# intex_spa_V4.net
KiCad netlist of a schematic drawn in EAGLE
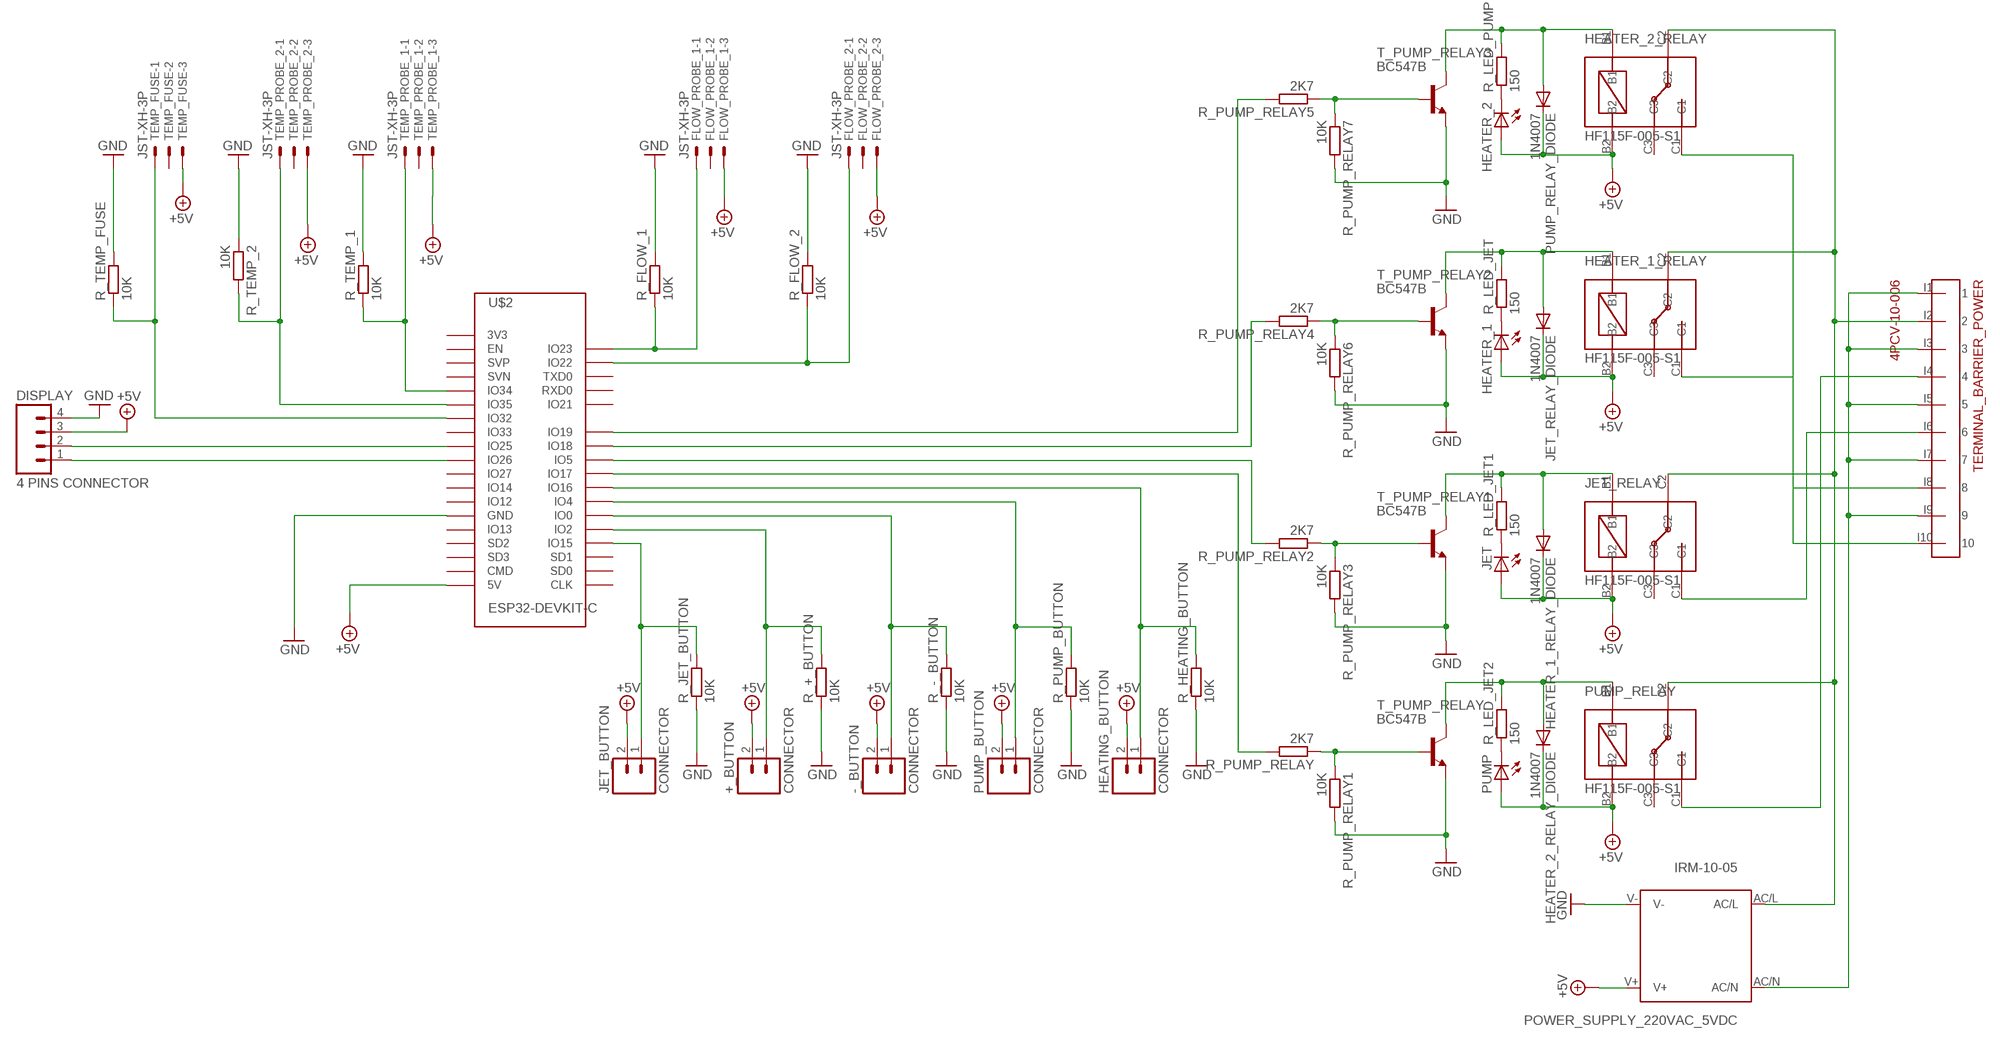
[diagram p0: schematic, sheet 1]

(export (version "E")
  (design (tool "Eeschema 10.0.6"))
  (components
    (comp (ref "+_BUTTON")
      (value "CONNECTOR")
      (footprint "eagle-import:JST-2-PTH-VERT")
      (libsource (lib "eagle-import") (part "M02JST-PTH-VERT"))
    )
    (comp (ref "-_BUTTON")
      (value "CONNECTOR")
      (footprint "eagle-import:JST-2-PTH-VERT")
      (libsource (lib "eagle-import") (part "M02JST-PTH-VERT"))
    )
    (comp (ref "DISPLAY")
      (value "4 PINS CONNECTOR")
      (footprint "eagle-import:1X04")
      (libsource (lib "eagle-import") (part "M04PTH"))
    )
    (comp (ref "FLOW_PROBE_1")
      (value "JST-XH-3P")
      (footprint "eagle-import:JST-XH-03-PACKAGE-LONG-PAD")
      (libsource (lib "eagle-import") (part "JST-XH-03-PIN-LONG-PAD"))
    )
    (comp (ref "FLOW_PROBE_2")
      (value "JST-XH-3P")
      (footprint "eagle-import:JST-XH-03-PACKAGE-LONG-PAD")
      (libsource (lib "eagle-import") (part "JST-XH-03-PIN-LONG-PAD"))
    )
    (comp (ref "HEATER_1")
      (value "LED3MM")
      (footprint "eagle-import:LED3MM")
      (libsource (lib "eagle-import") (part "LED3MM"))
    )
    (comp (ref "HEATER_1_RELAY")
      (value "HF115F-005-S1")
      (footprint "eagle-import:HF115F-005-S1")
      (libsource (lib "eagle-import") (part "HF115F-005-S1"))
    )
    (comp (ref "HEATER_1_RELAY_DIODE")
      (value "1N4007")
      (footprint "eagle-import:DO41-10")
      (libsource (lib "eagle-import") (part "1N4004"))
    )
    (comp (ref "HEATER_2")
      (value "LED3MM")
      (footprint "eagle-import:LED3MM")
      (libsource (lib "eagle-import") (part "LED3MM"))
    )
    (comp (ref "HEATER_2_RELAY")
      (value "HF115F-005-S1")
      (footprint "eagle-import:HF115F-005-S1")
      (libsource (lib "eagle-import") (part "HF115F-005-S1"))
    )
    (comp (ref "HEATER_2_RELAY_DIODE")
      (value "1N4007")
      (footprint "eagle-import:DO41-10")
      (libsource (lib "eagle-import") (part "1N4004"))
    )
    (comp (ref "HEATING_BUTTON")
      (value "CONNECTOR")
      (footprint "eagle-import:JST-2-PTH-VERT")
      (libsource (lib "eagle-import") (part "M02JST-PTH-VERT"))
    )
    (comp (ref "JET")
      (value "LED3MM")
      (footprint "eagle-import:LED3MM")
      (libsource (lib "eagle-import") (part "LED3MM"))
    )
    (comp (ref "JET_BUTTON")
      (value "CONNECTOR")
      (footprint "eagle-import:JST-2-PTH-VERT")
      (libsource (lib "eagle-import") (part "M02JST-PTH-VERT"))
    )
    (comp (ref "JET_RELAY")
      (value "HF115F-005-S1")
      (footprint "eagle-import:HF115F-005-S1")
      (libsource (lib "eagle-import") (part "HF115F-005-S1"))
    )
    (comp (ref "JET_RELAY_DIODE")
      (value "1N4007")
      (footprint "eagle-import:DO41-10")
      (libsource (lib "eagle-import") (part "1N4004"))
    )
    (comp (ref "POWER_SUPPLY_220VAC_5VDC")
      (value "IRM-10-05")
      (footprint "eagle-import:IRM_05_10")
      (libsource (lib "eagle-import") (part "IRM_05/10IRM_05/10"))
    )
    (comp (ref "PUMP")
      (value "LED3MM")
      (footprint "eagle-import:LED3MM")
      (libsource (lib "eagle-import") (part "LED3MM"))
    )
    (comp (ref "PUMP_BUTTON")
      (value "CONNECTOR")
      (footprint "eagle-import:JST-2-PTH-VERT")
      (libsource (lib "eagle-import") (part "M02JST-PTH-VERT"))
    )
    (comp (ref "PUMP_RELAY")
      (value "HF115F-005-S1")
      (footprint "eagle-import:HF115F-005-S1")
      (libsource (lib "eagle-import") (part "HF115F-005-S1"))
    )
    (comp (ref "PUMP_RELAY_DIODE")
      (value "1N4007")
      (footprint "eagle-import:DO41-10")
      (libsource (lib "eagle-import") (part "1N4004"))
    )
    (comp (ref "R_+_BUTTON")
      (value "10K")
      (footprint "eagle-import:0204_5")
      (libsource (lib "eagle-import") (part "R-EU_0204/5"))
    )
    (comp (ref "R_-_BUTTON")
      (value "10K")
      (footprint "eagle-import:0204_5")
      (libsource (lib "eagle-import") (part "R-EU_0204/5"))
    )
    (comp (ref "R_FLOW_1")
      (value "10K")
      (footprint "eagle-import:0207_10")
      (libsource (lib "eagle-import") (part "R-EU_0207/10"))
    )
    (comp (ref "R_FLOW_2")
      (value "10K")
      (footprint "eagle-import:0207_10")
      (libsource (lib "eagle-import") (part "R-EU_0207/10"))
    )
    (comp (ref "R_HEATING_BUTTON")
      (value "10K")
      (footprint "eagle-import:0204_5")
      (libsource (lib "eagle-import") (part "R-EU_0204/5"))
    )
    (comp (ref "R_JET_BUTTON")
      (value "10K")
      (footprint "eagle-import:0204_5")
      (libsource (lib "eagle-import") (part "R-EU_0204/5"))
    )
    (comp (ref "R_LED_JET")
      (value "150")
      (footprint "eagle-import:0204_5")
      (libsource (lib "eagle-import") (part "resistor_R-EU_0204/5"))
    )
    (comp (ref "R_LED_JET1")
      (value "150")
      (footprint "eagle-import:0204_5")
      (libsource (lib "eagle-import") (part "resistor_R-EU_0204/5"))
    )
    (comp (ref "R_LED_JET2")
      (value "150")
      (footprint "eagle-import:0204_5")
      (libsource (lib "eagle-import") (part "resistor_R-EU_0204/5"))
    )
    (comp (ref "R_LED_PUMP")
      (value "150")
      (footprint "eagle-import:0204_5")
      (libsource (lib "eagle-import") (part "resistor_R-EU_0204/5"))
    )
    (comp (ref "R_PUMP_BUTTON")
      (value "10K")
      (footprint "eagle-import:0204_5")
      (libsource (lib "eagle-import") (part "R-EU_0204/5"))
    )
    (comp (ref "R_PUMP_RELAY")
      (value "2K7")
      (footprint "eagle-import:0204_5")
      (libsource (lib "eagle-import") (part "R-EU_0204/5"))
    )
    (comp (ref "R_PUMP_RELAY1")
      (value "10K")
      (footprint "eagle-import:0204_5")
      (libsource (lib "eagle-import") (part "R-EU_0204/5"))
    )
    (comp (ref "R_PUMP_RELAY2")
      (value "2K7")
      (footprint "eagle-import:0204_5")
      (libsource (lib "eagle-import") (part "R-EU_0204/5"))
    )
    (comp (ref "R_PUMP_RELAY3")
      (value "10K")
      (footprint "eagle-import:0204_5")
      (libsource (lib "eagle-import") (part "R-EU_0204/5"))
    )
    (comp (ref "R_PUMP_RELAY4")
      (value "2K7")
      (footprint "eagle-import:0204_5")
      (libsource (lib "eagle-import") (part "R-EU_0204/5"))
    )
    (comp (ref "R_PUMP_RELAY5")
      (value "2K7")
      (footprint "eagle-import:0204_5")
      (libsource (lib "eagle-import") (part "R-EU_0204/5"))
    )
    (comp (ref "R_PUMP_RELAY6")
      (value "10K")
      (footprint "eagle-import:0204_5")
      (libsource (lib "eagle-import") (part "R-EU_0204/5"))
    )
    (comp (ref "R_PUMP_RELAY7")
      (value "10K")
      (footprint "eagle-import:0204_5")
      (libsource (lib "eagle-import") (part "R-EU_0204/5"))
    )
    (comp (ref "R_TEMP_1")
      (value "10K")
      (footprint "eagle-import:0207_10")
      (libsource (lib "eagle-import") (part "R-EU_0207/10"))
    )
    (comp (ref "R_TEMP_2")
      (value "10K")
      (footprint "eagle-import:0207_10")
      (libsource (lib "eagle-import") (part "R-EU_0207/10"))
    )
    (comp (ref "R_TEMP_FUSE")
      (value "10K")
      (footprint "eagle-import:0207_10")
      (libsource (lib "eagle-import") (part "R-EU_0207/10"))
    )
    (comp (ref "TEMP_FUSE")
      (value "JST-XH-3P")
      (footprint "eagle-import:JST-XH-03-PACKAGE-LONG-PAD")
      (libsource (lib "eagle-import") (part "JST-XH-03-PIN-LONG-PAD"))
    )
    (comp (ref "TEMP_PROBE_1")
      (value "JST-XH-3P")
      (footprint "eagle-import:JST-XH-03-PACKAGE-LONG-PAD")
      (libsource (lib "eagle-import") (part "JST-XH-03-PIN-LONG-PAD"))
    )
    (comp (ref "TEMP_PROBE_2")
      (value "JST-XH-3P")
      (footprint "eagle-import:JST-XH-03-PACKAGE-LONG-PAD")
      (libsource (lib "eagle-import") (part "JST-XH-03-PIN-LONG-PAD"))
    )
    (comp (ref "TERMINAL_BARRIER_POWER")
      (value "4PCV-10-006")
      (footprint "eagle-import:4PCV-10-006")
      (libsource (lib "eagle-import") (part "4PCV-10-006"))
    )
    (comp (ref "T_PUMP_RELAY")
      (value "BC547B")
      (footprint "eagle-import:TO92")
      (libsource (lib "eagle-import") (part "BC547B"))
    )
    (comp (ref "T_PUMP_RELAY1")
      (value "BC547B")
      (footprint "eagle-import:TO92")
      (libsource (lib "eagle-import") (part "BC547B"))
    )
    (comp (ref "T_PUMP_RELAY2")
      (value "BC547B")
      (footprint "eagle-import:TO92")
      (libsource (lib "eagle-import") (part "BC547B"))
    )
    (comp (ref "T_PUMP_RELAY3")
      (value "BC547B")
      (footprint "eagle-import:TO92")
      (libsource (lib "eagle-import") (part "BC547B"))
    )
    (comp (ref "U$2")
      (value "ESP32-DEVKIT-C")
      (footprint "eagle-import:ESP32-DEVKIT-C")
      (libsource (lib "eagle-import") (part "ESP32-DEVKIT-C"))
    )
  )
  (nets
    (net (code "1") (name "+5V") (class "Default")
      (node (ref "+_BUTTON") (pin "2") (pinfunction "2_2") (pintype "passive"))
      (node (ref "-_BUTTON") (pin "2") (pinfunction "2_2") (pintype "passive"))
      (node (ref "DISPLAY") (pin "3") (pinfunction "3_3") (pintype "passive"))
      (node (ref "FLOW_PROBE_1") (pin "3") (pinfunction "S_3") (pintype "passive"))
      (node (ref "FLOW_PROBE_2") (pin "3") (pinfunction "S_3") (pintype "passive"))
      (node (ref "HEATER_1") (pin "A") (pinfunction "A_A") (pintype "passive"))
      (node (ref "HEATER_1_RELAY") (pin "B2") (pinfunction "B2_B2") (pintype "bidirectional"))
      (node (ref "HEATER_1_RELAY_DIODE") (pin "C") (pinfunction "C_C") (pintype "passive"))
      (node (ref "HEATER_2") (pin "A") (pinfunction "A_A") (pintype "passive"))
      (node (ref "HEATER_2_RELAY") (pin "B2") (pinfunction "B2_B2") (pintype "bidirectional"))
      (node (ref "HEATER_2_RELAY_DIODE") (pin "C") (pinfunction "C_C") (pintype "passive"))
      (node (ref "HEATING_BUTTON") (pin "2") (pinfunction "2_2") (pintype "passive"))
      (node (ref "JET") (pin "A") (pinfunction "A_A") (pintype "passive"))
      (node (ref "JET_BUTTON") (pin "2") (pinfunction "2_2") (pintype "passive"))
      (node (ref "JET_RELAY") (pin "B2") (pinfunction "B2_B2") (pintype "bidirectional"))
      (node (ref "JET_RELAY_DIODE") (pin "C") (pinfunction "C_C") (pintype "passive"))
      (node (ref "POWER_SUPPLY_220VAC_5VDC") (pin "V+") (pinfunction "V+_V+") (pintype "output"))
      (node (ref "PUMP") (pin "A") (pinfunction "A_A") (pintype "passive"))
      (node (ref "PUMP_BUTTON") (pin "2") (pinfunction "2_2") (pintype "passive"))
      (node (ref "PUMP_RELAY") (pin "B2") (pinfunction "B2_B2") (pintype "bidirectional"))
      (node (ref "PUMP_RELAY_DIODE") (pin "C") (pinfunction "C_C") (pintype "passive"))
      (node (ref "TEMP_FUSE") (pin "3") (pinfunction "S_3") (pintype "passive"))
      (node (ref "TEMP_PROBE_1") (pin "3") (pinfunction "S_3") (pintype "passive"))
      (node (ref "TEMP_PROBE_2") (pin "3") (pinfunction "S_3") (pintype "passive"))
      (node (ref "U$2") (pin "5V") (pinfunction "5V_5V") (pintype "bidirectional"))
    )
    (net (code "2") (name "GND") (class "Default")
      (node (ref "DISPLAY") (pin "4") (pinfunction "4_4") (pintype "passive"))
      (node (ref "POWER_SUPPLY_220VAC_5VDC") (pin "V-") (pinfunction "V-_V-") (pintype "output"))
      (node (ref "R_+_BUTTON") (pin "1") (pinfunction "1_1") (pintype "passive"))
      (node (ref "R_-_BUTTON") (pin "1") (pinfunction "1_1") (pintype "passive"))
      (node (ref "R_FLOW_1") (pin "2") (pinfunction "2_2") (pintype "passive"))
      (node (ref "R_FLOW_2") (pin "2") (pinfunction "2_2") (pintype "passive"))
      (node (ref "R_HEATING_BUTTON") (pin "1") (pinfunction "1_1") (pintype "passive"))
      (node (ref "R_JET_BUTTON") (pin "1") (pinfunction "1_1") (pintype "passive"))
      (node (ref "R_PUMP_BUTTON") (pin "1") (pinfunction "1_1") (pintype "passive"))
      (node (ref "R_PUMP_RELAY1") (pin "2") (pinfunction "2_2") (pintype "passive"))
      (node (ref "R_PUMP_RELAY3") (pin "2") (pinfunction "2_2") (pintype "passive"))
      (node (ref "R_PUMP_RELAY6") (pin "2") (pinfunction "2_2") (pintype "passive"))
      (node (ref "R_PUMP_RELAY7") (pin "2") (pinfunction "2_2") (pintype "passive"))
      (node (ref "R_TEMP_1") (pin "2") (pinfunction "2_2") (pintype "passive"))
      (node (ref "R_TEMP_2") (pin "1") (pinfunction "1_1") (pintype "passive"))
      (node (ref "R_TEMP_FUSE") (pin "2") (pinfunction "2_2") (pintype "passive"))
      (node (ref "T_PUMP_RELAY") (pin "1") (pinfunction "E_1") (pintype "passive"))
      (node (ref "T_PUMP_RELAY1") (pin "1") (pinfunction "E_1") (pintype "passive"))
      (node (ref "T_PUMP_RELAY2") (pin "1") (pinfunction "E_1") (pintype "passive"))
      (node (ref "T_PUMP_RELAY3") (pin "1") (pinfunction "E_1") (pintype "passive"))
      (node (ref "U$2") (pin "GND") (pinfunction "GND_GND") (pintype "bidirectional"))
      (node (ref "U$2") (pin "GND2") (pinfunction "GND_GND2") (pintype "bidirectional"))
      (node (ref "U$2") (pin "GND3") (pinfunction "GND_GND3") (pintype "bidirectional"))
    )
    (net (code "3") (name "Net-(+_BUTTON-Pad1)") (class "Default")
      (node (ref "+_BUTTON") (pin "1") (pinfunction "1_1") (pintype "passive"))
      (node (ref "R_+_BUTTON") (pin "2") (pinfunction "2_2") (pintype "passive"))
      (node (ref "U$2") (pin "IO2") (pinfunction "IO2_IO2") (pintype "bidirectional"))
    )
    (net (code "4") (name "Net-(-_BUTTON-Pad1)") (class "Default")
      (node (ref "-_BUTTON") (pin "1") (pinfunction "1_1") (pintype "passive"))
      (node (ref "R_-_BUTTON") (pin "2") (pinfunction "2_2") (pintype "passive"))
      (node (ref "U$2") (pin "IO0") (pinfunction "IO0_IO0") (pintype "bidirectional"))
    )
    (net (code "5") (name "Net-(DISPLAY-Pad1)") (class "Default")
      (node (ref "DISPLAY") (pin "1") (pinfunction "1_1") (pintype "passive"))
      (node (ref "U$2") (pin "IO26") (pinfunction "IO26_IO26") (pintype "bidirectional"))
    )
    (net (code "6") (name "Net-(DISPLAY-Pad2)") (class "Default")
      (node (ref "DISPLAY") (pin "2") (pinfunction "2_2") (pintype "passive"))
      (node (ref "U$2") (pin "IO25") (pinfunction "IO25_IO25") (pintype "bidirectional"))
    )
    (net (code "7") (name "Net-(FLOW_PROBE_1A-S)") (class "Default")
      (node (ref "FLOW_PROBE_1") (pin "1") (pinfunction "S_1") (pintype "passive"))
      (node (ref "R_FLOW_1") (pin "1") (pinfunction "1_1") (pintype "passive"))
      (node (ref "U$2") (pin "IO23") (pinfunction "IO23_IO23") (pintype "bidirectional"))
    )
    (net (code "8") (name "Net-(FLOW_PROBE_2A-S)") (class "Default")
      (node (ref "FLOW_PROBE_2") (pin "1") (pinfunction "S_1") (pintype "passive"))
      (node (ref "R_FLOW_2") (pin "1") (pinfunction "1_1") (pintype "passive"))
      (node (ref "U$2") (pin "IO22") (pinfunction "IO22_IO22") (pintype "bidirectional"))
    )
    (net (code "9") (name "Net-(HEATER_1-C)") (class "Default")
      (node (ref "HEATER_1") (pin "K") (pinfunction "C_K") (pintype "passive"))
      (node (ref "R_LED_JET") (pin "1") (pinfunction "1_1") (pintype "passive"))
    )
    (net (code "10") (name "Net-(HEATER_1_RELAY-PadC1)") (class "Default")
      (node (ref "HEATER_1_RELAY") (pin "C1") (pinfunction "C1_C1") (pintype "bidirectional"))
      (node (ref "TERMINAL_BARRIER_POWER") (pin "I8") (pinfunction "I8_I8") (pintype "bidirectional"))
    )
    (net (code "11") (name "Net-(HEATER_1_RELAY-PadC2)") (class "Default")
      (node (ref "HEATER_1_RELAY") (pin "C2") (pinfunction "C2_C2") (pintype "bidirectional"))
      (node (ref "HEATER_2_RELAY") (pin "C2") (pinfunction "C2_C2") (pintype "bidirectional"))
      (node (ref "JET_RELAY") (pin "C2") (pinfunction "C2_C2") (pintype "bidirectional"))
      (node (ref "POWER_SUPPLY_220VAC_5VDC") (pin "AC/L") (pinfunction "AC/L_AC/L") (pintype "input"))
      (node (ref "PUMP_RELAY") (pin "C2") (pinfunction "C2_C2") (pintype "bidirectional"))
      (node (ref "TERMINAL_BARRIER_POWER") (pin "I2") (pinfunction "I2_I2") (pintype "bidirectional"))
    )
    (net (code "12") (name "Net-(HEATER_2-C)") (class "Default")
      (node (ref "HEATER_2") (pin "K") (pinfunction "C_K") (pintype "passive"))
      (node (ref "R_LED_PUMP") (pin "1") (pinfunction "1_1") (pintype "passive"))
    )
    (net (code "13") (name "Net-(HEATER_2_RELAY-PadC1)") (class "Default")
      (node (ref "HEATER_2_RELAY") (pin "C1") (pinfunction "C1_C1") (pintype "bidirectional"))
      (node (ref "TERMINAL_BARRIER_POWER") (pin "I10") (pinfunction "I10_I10") (pintype "bidirectional"))
    )
    (net (code "14") (name "Net-(HEATING_BUTTON-Pad1)") (class "Default")
      (node (ref "HEATING_BUTTON") (pin "1") (pinfunction "1_1") (pintype "passive"))
      (node (ref "R_HEATING_BUTTON") (pin "2") (pinfunction "2_2") (pintype "passive"))
      (node (ref "U$2") (pin "IO16") (pinfunction "IO16_IO16") (pintype "bidirectional"))
    )
    (net (code "15") (name "Net-(JET-C)") (class "Default")
      (node (ref "JET") (pin "K") (pinfunction "C_K") (pintype "passive"))
      (node (ref "R_LED_JET1") (pin "1") (pinfunction "1_1") (pintype "passive"))
    )
    (net (code "16") (name "Net-(JET_BUTTON-Pad1)") (class "Default")
      (node (ref "JET_BUTTON") (pin "1") (pinfunction "1_1") (pintype "passive"))
      (node (ref "R_JET_BUTTON") (pin "2") (pinfunction "2_2") (pintype "passive"))
      (node (ref "U$2") (pin "IO15") (pinfunction "IO15_IO15") (pintype "bidirectional"))
    )
    (net (code "17") (name "Net-(JET_RELAY-PadC1)") (class "Default")
      (node (ref "JET_RELAY") (pin "C1") (pinfunction "C1_C1") (pintype "bidirectional"))
      (node (ref "TERMINAL_BARRIER_POWER") (pin "I6") (pinfunction "I6_I6") (pintype "bidirectional"))
    )
    (net (code "18") (name "Net-(POWER_SUPPLY_220VAC_5VDC-PadAC{slash}N)") (class "Default")
      (node (ref "POWER_SUPPLY_220VAC_5VDC") (pin "AC/N") (pinfunction "AC/N_AC/N") (pintype "input"))
      (node (ref "TERMINAL_BARRIER_POWER") (pin "I1") (pinfunction "I1_I1") (pintype "bidirectional"))
      (node (ref "TERMINAL_BARRIER_POWER") (pin "I3") (pinfunction "I3_I3") (pintype "bidirectional"))
      (node (ref "TERMINAL_BARRIER_POWER") (pin "I5") (pinfunction "I5_I5") (pintype "bidirectional"))
      (node (ref "TERMINAL_BARRIER_POWER") (pin "I7") (pinfunction "I7_I7") (pintype "bidirectional"))
      (node (ref "TERMINAL_BARRIER_POWER") (pin "I9") (pinfunction "I9_I9") (pintype "bidirectional"))
    )
    (net (code "19") (name "Net-(PUMP-C)") (class "Default")
      (node (ref "PUMP") (pin "K") (pinfunction "C_K") (pintype "passive"))
      (node (ref "R_LED_JET2") (pin "1") (pinfunction "1_1") (pintype "passive"))
    )
    (net (code "20") (name "Net-(PUMP_BUTTON-Pad1)") (class "Default")
      (node (ref "PUMP_BUTTON") (pin "1") (pinfunction "1_1") (pintype "passive"))
      (node (ref "R_PUMP_BUTTON") (pin "2") (pinfunction "2_2") (pintype "passive"))
      (node (ref "U$2") (pin "IO4") (pinfunction "IO4_IO4") (pintype "bidirectional"))
    )
    (net (code "21") (name "Net-(PUMP_RELAY-PadC1)") (class "Default")
      (node (ref "PUMP_RELAY") (pin "C1") (pinfunction "C1_C1") (pintype "bidirectional"))
      (node (ref "TERMINAL_BARRIER_POWER") (pin "I4") (pinfunction "I4_I4") (pintype "bidirectional"))
    )
    (net (code "22") (name "Net-(R_PUMP_RELAY-Pad2)") (class "Default")
      (node (ref "R_PUMP_RELAY") (pin "2") (pinfunction "2_2") (pintype "passive"))
      (node (ref "U$2") (pin "IO17") (pinfunction "IO17_IO17") (pintype "bidirectional"))
    )
    (net (code "23") (name "Net-(R_PUMP_RELAY2-Pad2)") (class "Default")
      (node (ref "R_PUMP_RELAY2") (pin "2") (pinfunction "2_2") (pintype "passive"))
      (node (ref "U$2") (pin "IO5") (pinfunction "IO5_IO5") (pintype "bidirectional"))
    )
    (net (code "24") (name "Net-(R_PUMP_RELAY4-Pad2)") (class "Default")
      (node (ref "R_PUMP_RELAY4") (pin "2") (pinfunction "2_2") (pintype "passive"))
      (node (ref "U$2") (pin "IO18") (pinfunction "IO18_IO18") (pintype "bidirectional"))
    )
    (net (code "25") (name "Net-(R_PUMP_RELAY5-Pad2)") (class "Default")
      (node (ref "R_PUMP_RELAY5") (pin "2") (pinfunction "2_2") (pintype "passive"))
      (node (ref "U$2") (pin "IO19") (pinfunction "IO19_IO19") (pintype "bidirectional"))
    )
    (net (code "26") (name "Net-(TEMP_FUSEA-S)") (class "Default")
      (node (ref "R_TEMP_FUSE") (pin "1") (pinfunction "1_1") (pintype "passive"))
      (node (ref "TEMP_FUSE") (pin "1") (pinfunction "S_1") (pintype "passive"))
      (node (ref "U$2") (pin "IO32") (pinfunction "IO32_IO32") (pintype "bidirectional"))
    )
    (net (code "27") (name "Net-(TEMP_PROBE_1A-S)") (class "Default")
      (node (ref "R_TEMP_1") (pin "1") (pinfunction "1_1") (pintype "passive"))
      (node (ref "TEMP_PROBE_1") (pin "1") (pinfunction "S_1") (pintype "passive"))
      (node (ref "U$2") (pin "IO34") (pinfunction "IO34_IO34") (pintype "bidirectional"))
    )
    (net (code "28") (name "Net-(TEMP_PROBE_2A-S)") (class "Default")
      (node (ref "R_TEMP_2") (pin "2") (pinfunction "2_2") (pintype "passive"))
      (node (ref "TEMP_PROBE_2") (pin "1") (pinfunction "S_1") (pintype "passive"))
      (node (ref "U$2") (pin "IO35") (pinfunction "IO35_IO35") (pintype "bidirectional"))
    )
    (net (code "29") (name "Net-(T_PUMP_RELAY-B)") (class "Default")
      (node (ref "R_PUMP_RELAY") (pin "1") (pinfunction "1_1") (pintype "passive"))
      (node (ref "R_PUMP_RELAY1") (pin "1") (pinfunction "1_1") (pintype "passive"))
      (node (ref "T_PUMP_RELAY") (pin "2") (pinfunction "B_2") (pintype "passive"))
    )
    (net (code "30") (name "Net-(T_PUMP_RELAY-C)") (class "Default")
      (node (ref "HEATER_2_RELAY_DIODE") (pin "A") (pinfunction "A_A") (pintype "passive"))
      (node (ref "PUMP_RELAY") (pin "B1") (pinfunction "B1_B1") (pintype "bidirectional"))
      (node (ref "R_LED_JET2") (pin "2") (pinfunction "2_2") (pintype "passive"))
      (node (ref "T_PUMP_RELAY") (pin "3") (pinfunction "C_3") (pintype "passive"))
    )
    (net (code "31") (name "Net-(T_PUMP_RELAY1-B)") (class "Default")
      (node (ref "R_PUMP_RELAY2") (pin "1") (pinfunction "1_1") (pintype "passive"))
      (node (ref "R_PUMP_RELAY3") (pin "1") (pinfunction "1_1") (pintype "passive"))
      (node (ref "T_PUMP_RELAY1") (pin "2") (pinfunction "B_2") (pintype "passive"))
    )
    (net (code "32") (name "Net-(T_PUMP_RELAY1-C)") (class "Default")
      (node (ref "HEATER_1_RELAY_DIODE") (pin "A") (pinfunction "A_A") (pintype "passive"))
      (node (ref "JET_RELAY") (pin "B1") (pinfunction "B1_B1") (pintype "bidirectional"))
      (node (ref "R_LED_JET1") (pin "2") (pinfunction "2_2") (pintype "passive"))
      (node (ref "T_PUMP_RELAY1") (pin "3") (pinfunction "C_3") (pintype "passive"))
    )
    (net (code "33") (name "Net-(T_PUMP_RELAY2-B)") (class "Default")
      (node (ref "R_PUMP_RELAY4") (pin "1") (pinfunction "1_1") (pintype "passive"))
      (node (ref "R_PUMP_RELAY6") (pin "1") (pinfunction "1_1") (pintype "passive"))
      (node (ref "T_PUMP_RELAY2") (pin "2") (pinfunction "B_2") (pintype "passive"))
    )
    (net (code "34") (name "Net-(T_PUMP_RELAY2-C)") (class "Default")
      (node (ref "HEATER_1_RELAY") (pin "B1") (pinfunction "B1_B1") (pintype "bidirectional"))
      (node (ref "JET_RELAY_DIODE") (pin "A") (pinfunction "A_A") (pintype "passive"))
      (node (ref "R_LED_JET") (pin "2") (pinfunction "2_2") (pintype "passive"))
      (node (ref "T_PUMP_RELAY2") (pin "3") (pinfunction "C_3") (pintype "passive"))
    )
    (net (code "35") (name "Net-(T_PUMP_RELAY3-B)") (class "Default")
      (node (ref "R_PUMP_RELAY5") (pin "1") (pinfunction "1_1") (pintype "passive"))
      (node (ref "R_PUMP_RELAY7") (pin "1") (pinfunction "1_1") (pintype "passive"))
      (node (ref "T_PUMP_RELAY3") (pin "2") (pinfunction "B_2") (pintype "passive"))
    )
    (net (code "36") (name "Net-(T_PUMP_RELAY3-C)") (class "Default")
      (node (ref "HEATER_2_RELAY") (pin "B1") (pinfunction "B1_B1") (pintype "bidirectional"))
      (node (ref "PUMP_RELAY_DIODE") (pin "A") (pinfunction "A_A") (pintype "passive"))
      (node (ref "R_LED_PUMP") (pin "2") (pinfunction "2_2") (pintype "passive"))
      (node (ref "T_PUMP_RELAY3") (pin "3") (pinfunction "C_3") (pintype "passive"))
    )
    (net (code "37") (name "unconnected-(FLOW_PROBE_1B-S-Pad2)") (class "Default")
      (node (ref "FLOW_PROBE_1") (pin "2") (pinfunction "S_2") (pintype "passive"))
    )
    (net (code "38") (name "unconnected-(FLOW_PROBE_2B-S-Pad2)") (class "Default")
      (node (ref "FLOW_PROBE_2") (pin "2") (pinfunction "S_2") (pintype "passive"))
    )
    (net (code "39") (name "unconnected-(HEATER_1_RELAY-PadC3)") (class "Default")
      (node (ref "HEATER_1_RELAY") (pin "C3") (pinfunction "C3_C3") (pintype "bidirectional"))
    )
    (net (code "40") (name "unconnected-(HEATER_2_RELAY-PadC3)") (class "Default")
      (node (ref "HEATER_2_RELAY") (pin "C3") (pinfunction "C3_C3") (pintype "bidirectional"))
    )
    (net (code "41") (name "unconnected-(JET_RELAY-PadC3)") (class "Default")
      (node (ref "JET_RELAY") (pin "C3") (pinfunction "C3_C3") (pintype "bidirectional"))
    )
    (net (code "42") (name "unconnected-(PUMP_RELAY-PadC3)") (class "Default")
      (node (ref "PUMP_RELAY") (pin "C3") (pinfunction "C3_C3") (pintype "bidirectional"))
    )
    (net (code "43") (name "unconnected-(TEMP_FUSEB-S-Pad2)") (class "Default")
      (node (ref "TEMP_FUSE") (pin "2") (pinfunction "S_2") (pintype "passive"))
    )
    (net (code "44") (name "unconnected-(TEMP_PROBE_1B-S-Pad2)") (class "Default")
      (node (ref "TEMP_PROBE_1") (pin "2") (pinfunction "S_2") (pintype "passive"))
    )
    (net (code "45") (name "unconnected-(TEMP_PROBE_2B-S-Pad2)") (class "Default")
      (node (ref "TEMP_PROBE_2") (pin "2") (pinfunction "S_2") (pintype "passive"))
    )
    (net (code "46") (name "unconnected-(U$2-Pad3V3)") (class "Default")
      (node (ref "U$2") (pin "3V3") (pinfunction "3V3_3V3") (pintype "bidirectional"))
    )
    (net (code "47") (name "unconnected-(U$2-PadCLK)") (class "Default")
      (node (ref "U$2") (pin "CLK") (pinfunction "CLK_CLK") (pintype "bidirectional"))
    )
    (net (code "48") (name "unconnected-(U$2-PadCMD)") (class "Default")
      (node (ref "U$2") (pin "CMD") (pinfunction "CMD_CMD") (pintype "bidirectional"))
    )
    (net (code "49") (name "unconnected-(U$2-PadEN)") (class "Default")
      (node (ref "U$2") (pin "EN") (pinfunction "EN_EN") (pintype "bidirectional"))
    )
    (net (code "50") (name "unconnected-(U$2-PadIO12)") (class "Default")
      (node (ref "U$2") (pin "IO12") (pinfunction "IO12_IO12") (pintype "bidirectional"))
    )
    (net (code "51") (name "unconnected-(U$2-PadIO13)") (class "Default")
      (node (ref "U$2") (pin "IO13") (pinfunction "IO13_IO13") (pintype "bidirectional"))
    )
    (net (code "52") (name "unconnected-(U$2-PadIO14)") (class "Default")
      (node (ref "U$2") (pin "IO14") (pinfunction "IO14_IO14") (pintype "bidirectional"))
    )
    (net (code "53") (name "unconnected-(U$2-PadIO21)") (class "Default")
      (node (ref "U$2") (pin "IO21") (pinfunction "IO21_IO21") (pintype "bidirectional"))
    )
    (net (code "54") (name "unconnected-(U$2-PadIO27)") (class "Default")
      (node (ref "U$2") (pin "IO27") (pinfunction "IO27_IO27") (pintype "bidirectional"))
    )
    (net (code "55") (name "unconnected-(U$2-PadIO33)") (class "Default")
      (node (ref "U$2") (pin "IO33") (pinfunction "IO33_IO33") (pintype "bidirectional"))
    )
    (net (code "56") (name "unconnected-(U$2-PadRXD0)") (class "Default")
      (node (ref "U$2") (pin "RXD0") (pinfunction "RXD0_RXD0") (pintype "bidirectional"))
    )
    (net (code "57") (name "unconnected-(U$2-PadSD0)") (class "Default")
      (node (ref "U$2") (pin "SD0") (pinfunction "SD0_SD0") (pintype "bidirectional"))
    )
    (net (code "58") (name "unconnected-(U$2-PadSD1)") (class "Default")
      (node (ref "U$2") (pin "SD1") (pinfunction "SD1_SD1") (pintype "bidirectional"))
    )
    (net (code "59") (name "unconnected-(U$2-PadSD2)") (class "Default")
      (node (ref "U$2") (pin "SD2") (pinfunction "SD2_SD2") (pintype "bidirectional"))
    )
    (net (code "60") (name "unconnected-(U$2-PadSD3)") (class "Default")
      (node (ref "U$2") (pin "SD3") (pinfunction "SD3_SD3") (pintype "bidirectional"))
    )
    (net (code "61") (name "unconnected-(U$2-PadSVN)") (class "Default")
      (node (ref "U$2") (pin "SVN") (pinfunction "SVN_SVN") (pintype "bidirectional"))
    )
    (net (code "62") (name "unconnected-(U$2-PadSVP)") (class "Default")
      (node (ref "U$2") (pin "SVP") (pinfunction "SVP_SVP") (pintype "bidirectional"))
    )
    (net (code "63") (name "unconnected-(U$2-PadTXD0)") (class "Default")
      (node (ref "U$2") (pin "TXD0") (pinfunction "TXD0_TXD0") (pintype "bidirectional"))
    )
  )
)
